# main.net
KiCad netlist of a schematic drawn in Altium Designer
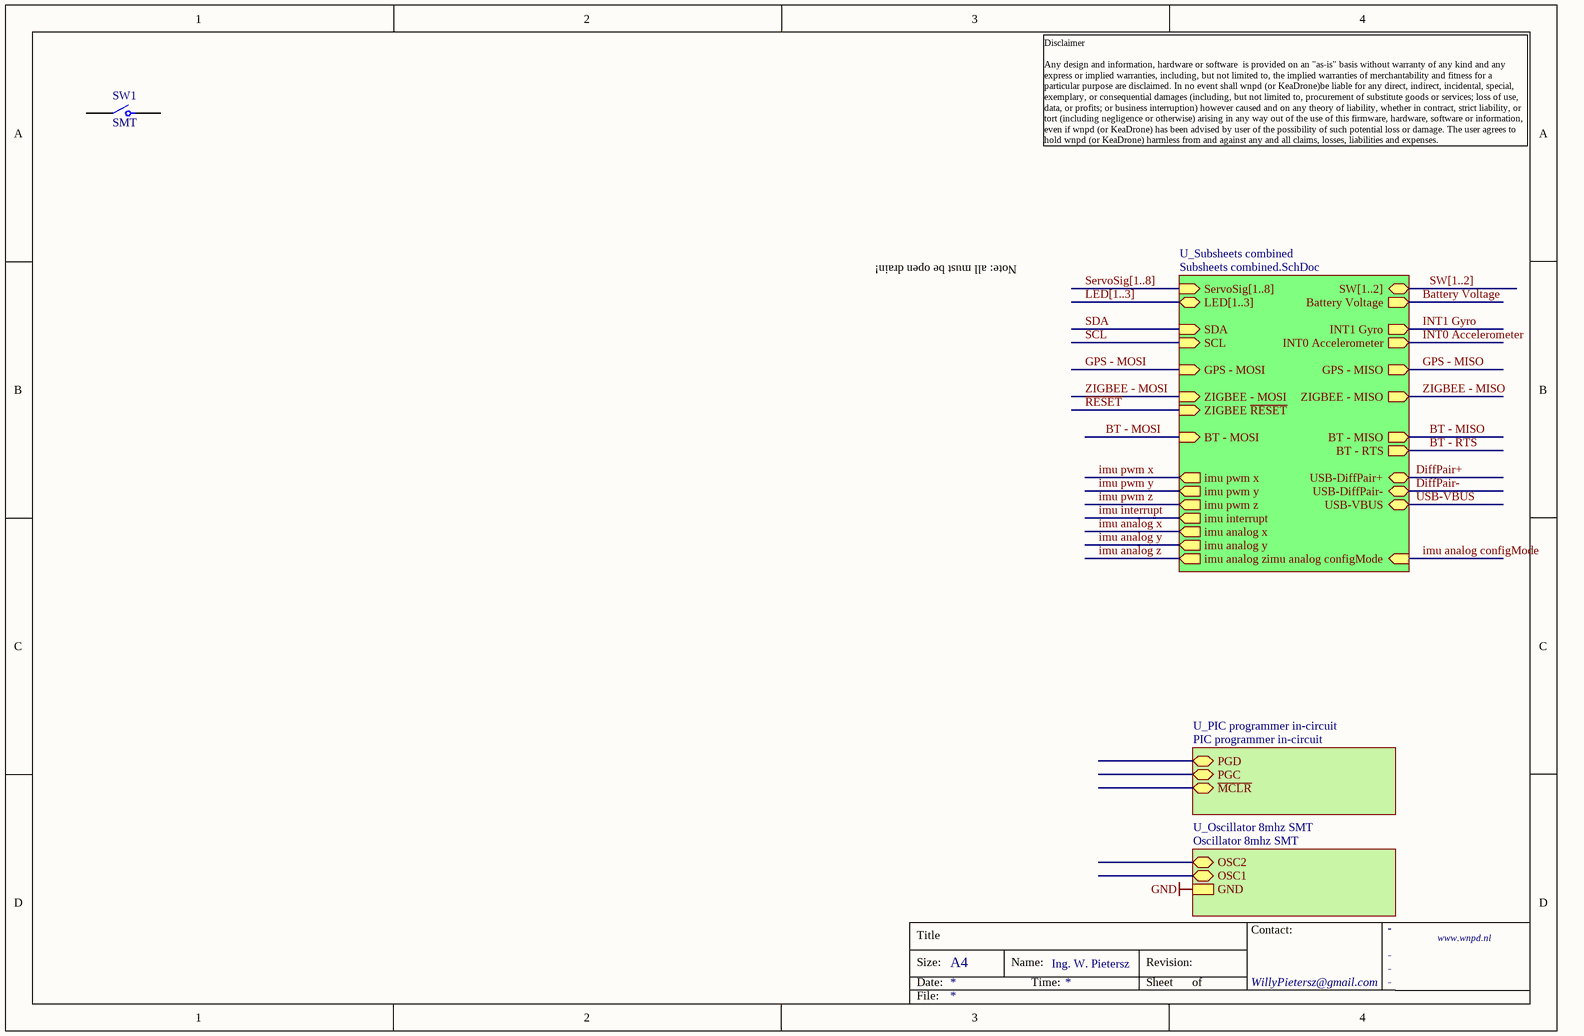
[diagram p0: main.SchDoc]

(export (version "E")
  (design (tool "Eeschema 10.0.6"))
  (components
    (comp (ref "SW1")
      (value "SMT")
      (footprint "SWITCH TACT")
      (description "Switch")
      (fields
        (field (name "PART NUMBER") "Pushbutton TACT")
        (field (name "VOLTAGE") "42")
        (field (name "AUTHOR") "Willem Pietersz")
      )
      (libsource (lib "OurDb") (part "SW-TACT"))
    )
  )
  (nets
    (net (code "47") (name "Net-(SW1-Pad1)") (class "Default")
      (node (ref "SW1") (pin "1") (pintype "passive"))
      (node (ref "SW1") (pin "4") (pintype "passive"))
    )
    (net (code "48") (name "Net-(SW1-Pad2)") (class "Default")
      (node (ref "SW1") (pin "2") (pintype "passive"))
      (node (ref "SW1") (pin "3") (pintype "passive"))
    )
  )
)
